# teensy_top.net
KiCad netlist of a schematic drawn in EAGLE
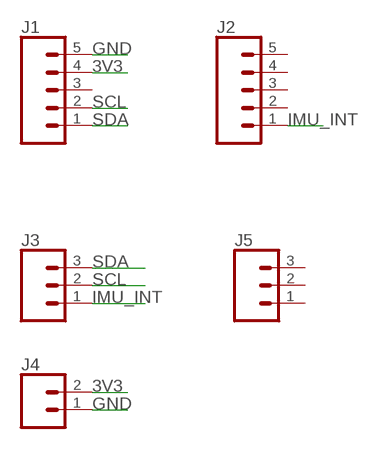
[diagram p0: schematic, sheet 1]

(export (version "E")
  (design (tool "Eeschema 10.0.6"))
  (components
    (comp (ref "J1")
      (value "CONN_05NO_SILK")
      (footprint "eagle-import:1X05_NO_SILK")
      (libsource (lib "eagle-import") (part "CONN_05NO_SILK"))
    )
    (comp (ref "J2")
      (value "CONN_05NO_SILK")
      (footprint "eagle-import:1X05_NO_SILK")
      (libsource (lib "eagle-import") (part "CONN_05NO_SILK"))
    )
    (comp (ref "J3")
      (value "CONN_031X03_NO_SILK")
      (footprint "eagle-import:1X03_NO_SILK")
      (libsource (lib "eagle-import") (part "CONN_031X03_NO_SILK"))
    )
    (comp (ref "J4")
      (value "CONN_021X02_NO_SILK")
      (footprint "eagle-import:1X02_NO_SILK")
      (libsource (lib "eagle-import") (part "CONN_021X02_NO_SILK"))
    )
    (comp (ref "J5")
      (value "CONN_031X03_NO_SILK")
      (footprint "eagle-import:1X03_NO_SILK")
      (libsource (lib "eagle-import") (part "CONN_031X03_NO_SILK"))
    )
  )
  (nets
    (net (code "1") (name "/3V3") (class "Default")
      (node (ref "J1") (pin "4") (pinfunction "4_4") (pintype "passive"))
      (node (ref "J4") (pin "2") (pinfunction "2_2") (pintype "passive"))
    )
    (net (code "2") (name "/GND") (class "Default")
      (node (ref "J1") (pin "5") (pinfunction "5_5") (pintype "passive"))
      (node (ref "J4") (pin "1") (pinfunction "1_1") (pintype "passive"))
    )
    (net (code "3") (name "/IMU_INT") (class "Default")
      (node (ref "J2") (pin "1") (pinfunction "1_1") (pintype "passive"))
      (node (ref "J3") (pin "1") (pinfunction "1_1") (pintype "passive"))
    )
    (net (code "4") (name "/SCL") (class "Default")
      (node (ref "J1") (pin "2") (pinfunction "2_2") (pintype "passive"))
      (node (ref "J3") (pin "2") (pinfunction "2_2") (pintype "passive"))
    )
    (net (code "5") (name "/SDA") (class "Default")
      (node (ref "J1") (pin "1") (pinfunction "1_1") (pintype "passive"))
      (node (ref "J3") (pin "3") (pinfunction "3_3") (pintype "passive"))
    )
    (net (code "6") (name "unconnected-(J1-Pad3)") (class "Default")
      (node (ref "J1") (pin "3") (pinfunction "3_3") (pintype "passive"))
    )
    (net (code "7") (name "unconnected-(J2-Pad2)") (class "Default")
      (node (ref "J2") (pin "2") (pinfunction "2_2") (pintype "passive"))
    )
    (net (code "8") (name "unconnected-(J2-Pad3)") (class "Default")
      (node (ref "J2") (pin "3") (pinfunction "3_3") (pintype "passive"))
    )
    (net (code "9") (name "unconnected-(J2-Pad4)") (class "Default")
      (node (ref "J2") (pin "4") (pinfunction "4_4") (pintype "passive"))
    )
    (net (code "10") (name "unconnected-(J2-Pad5)") (class "Default")
      (node (ref "J2") (pin "5") (pinfunction "5_5") (pintype "passive"))
    )
    (net (code "11") (name "unconnected-(J5-Pad1)") (class "Default")
      (node (ref "J5") (pin "1") (pinfunction "1_1") (pintype "passive"))
    )
    (net (code "12") (name "unconnected-(J5-Pad2)") (class "Default")
      (node (ref "J5") (pin "2") (pinfunction "2_2") (pintype "passive"))
    )
    (net (code "13") (name "unconnected-(J5-Pad3)") (class "Default")
      (node (ref "J5") (pin "3") (pinfunction "3_3") (pintype "passive"))
    )
  )
)
